# motion_detect.net
KiCad netlist of a schematic drawn in EAGLE
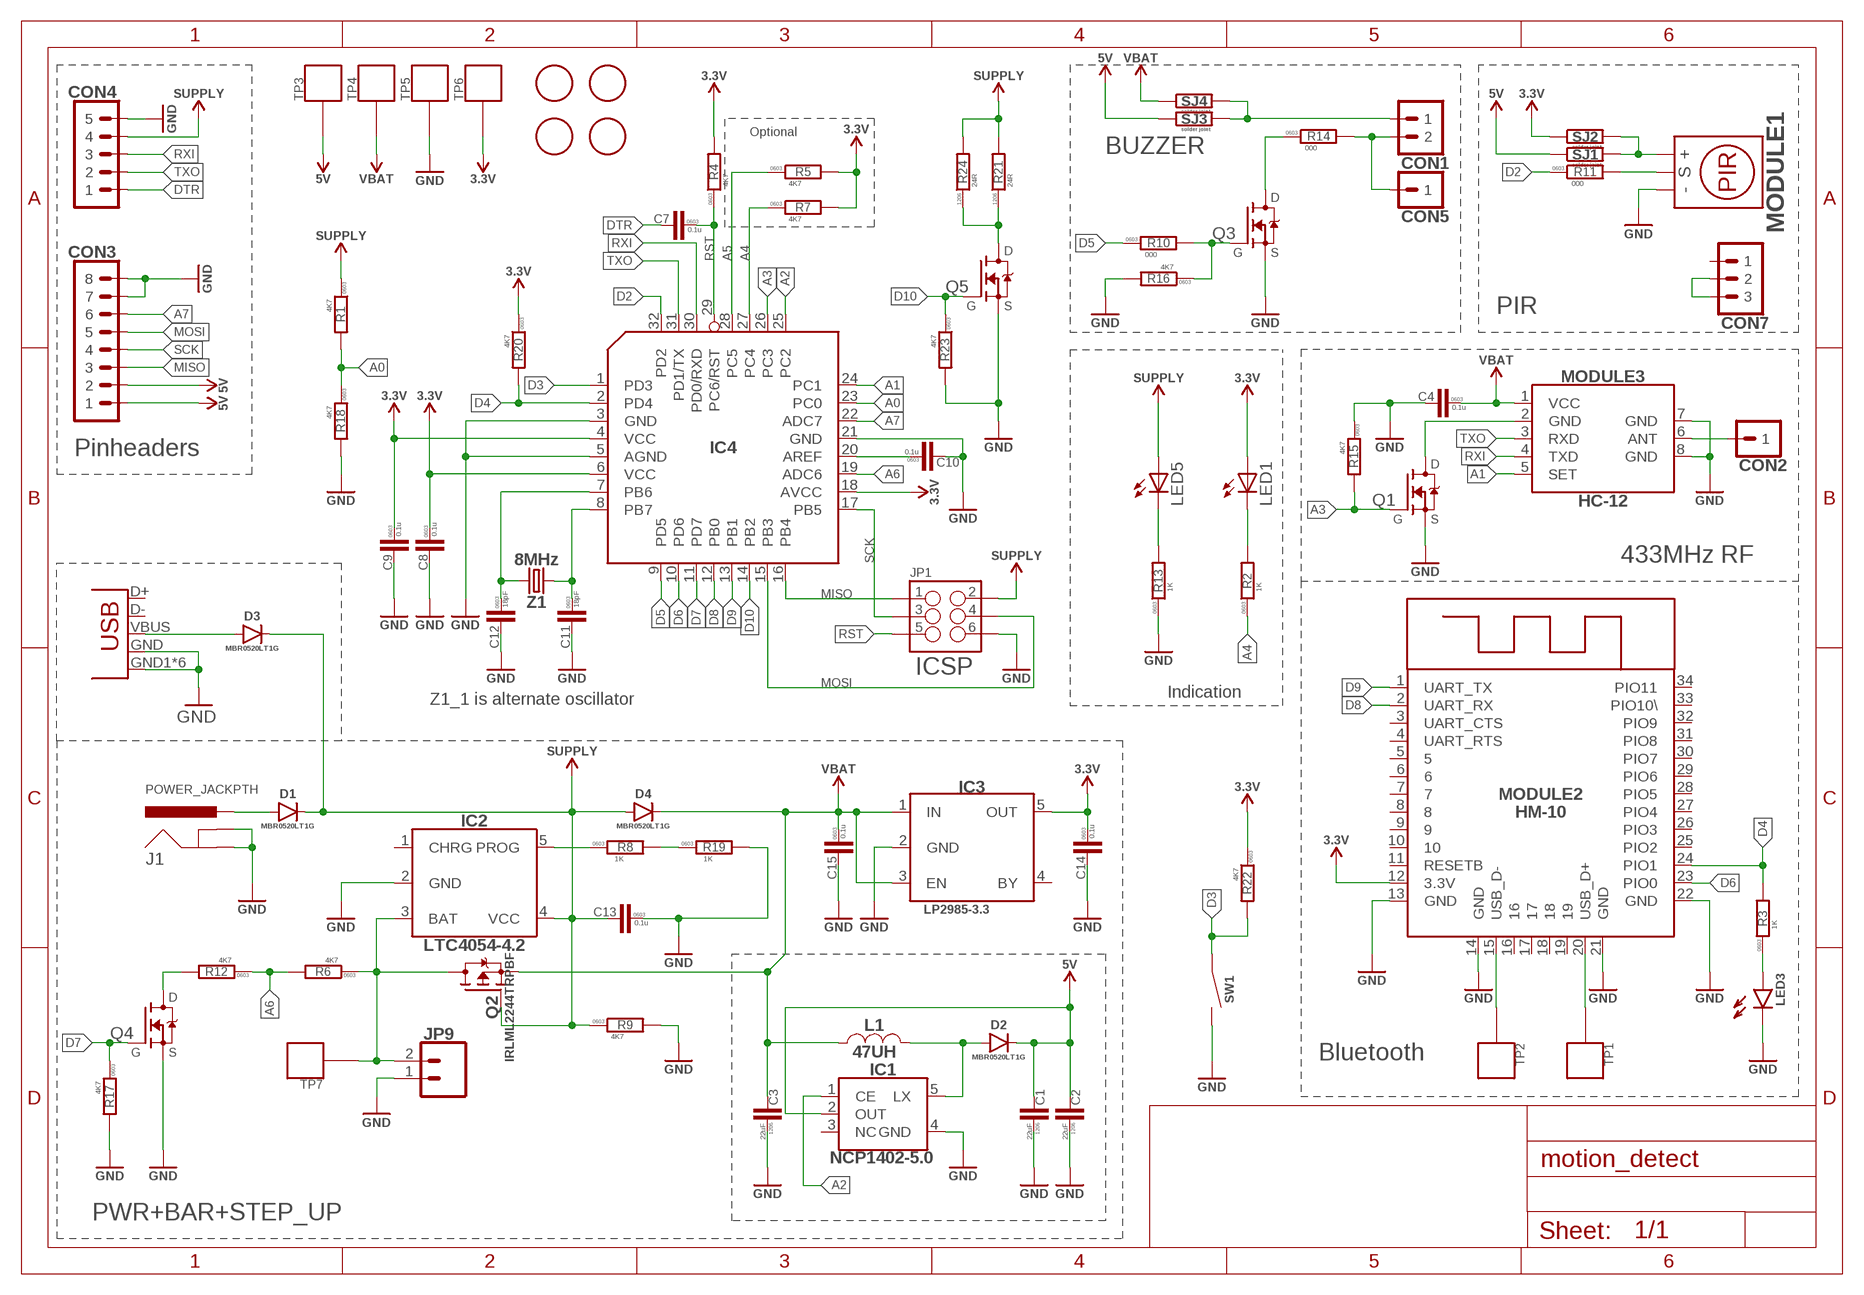
[diagram p0: schematic, sheet 1]

(export (version "E")
  (design (tool "Eeschema 10.0.6"))
  (components
    (comp (ref "C1")
      (value "22uF")
      (footprint "eagle-import:C1206")
      (libsource (lib "eagle-import") (part "C-1206"))
    )
    (comp (ref "C2")
      (value "22uF")
      (footprint "eagle-import:C1206")
      (libsource (lib "eagle-import") (part "C-1206"))
    )
    (comp (ref "C3")
      (value "22uF")
      (footprint "eagle-import:C1206")
      (libsource (lib "eagle-import") (part "C-1206"))
    )
    (comp (ref "C4")
      (value "0.1u")
      (footprint "eagle-import:C0603")
      (libsource (lib "eagle-import") (part "C-0603"))
    )
    (comp (ref "C7")
      (value "0.1u")
      (footprint "eagle-import:C0603")
      (libsource (lib "eagle-import") (part "C-0603"))
    )
    (comp (ref "C8")
      (value "0.1u")
      (footprint "eagle-import:C0603")
      (libsource (lib "eagle-import") (part "C-0603"))
    )
    (comp (ref "C9")
      (value "0.1u")
      (footprint "eagle-import:C0603")
      (libsource (lib "eagle-import") (part "C-0603"))
    )
    (comp (ref "C10")
      (value "0.1u")
      (footprint "eagle-import:C0603")
      (libsource (lib "eagle-import") (part "C-0603"))
    )
    (comp (ref "C11")
      (value "18pF")
      (footprint "eagle-import:C0603")
      (libsource (lib "eagle-import") (part "C-0603"))
    )
    (comp (ref "C12")
      (value "18pF")
      (footprint "eagle-import:C0603")
      (libsource (lib "eagle-import") (part "C-0603"))
    )
    (comp (ref "C13")
      (value "0.1u")
      (footprint "eagle-import:C0603")
      (libsource (lib "eagle-import") (part "C-0603"))
    )
    (comp (ref "C14")
      (value "0.1u")
      (footprint "eagle-import:C0603")
      (libsource (lib "eagle-import") (part "C-0603"))
    )
    (comp (ref "C15")
      (value "0.1u")
      (footprint "eagle-import:C0603")
      (libsource (lib "eagle-import") (part "C-0603"))
    )
    (comp (ref "CON1")
      (value "PINHEAD_1X02-2.54")
      (footprint "eagle-import:1X02-PTH-2.54")
      (libsource (lib "eagle-import") (part "PINHEAD_1X02-2.54"))
    )
    (comp (ref "CON2")
      (value "PINHEAD_1X01-2.54")
      (footprint "eagle-import:1X01-PTH-2.54")
      (libsource (lib "eagle-import") (part "PINHEAD_1X01-2.54"))
    )
    (comp (ref "CON3")
      (value "PINHEAD_1X08-2.54")
      (footprint "eagle-import:1X08-PTH-2.54")
      (libsource (lib "eagle-import") (part "PINHEAD_1X08-2.54"))
    )
    (comp (ref "CON4")
      (value "PINHEAD_1X05-2.54")
      (footprint "eagle-import:1X05-PTH-2.54")
      (libsource (lib "eagle-import") (part "PINHEAD_1X05-2.54"))
    )
    (comp (ref "CON5")
      (value "PINHEAD_1X01-2.54")
      (footprint "eagle-import:1X01-PTH-2.54")
      (libsource (lib "eagle-import") (part "PINHEAD_1X01-2.54"))
    )
    (comp (ref "CON6")
      (value "USB-2")
      (footprint "eagle-import:MICRO_USB_WITHOUT_PEGS")
      (fields (field (name "MANF") "FCI"))
      (libsource (lib "eagle-import") (part "USB-2"))
    )
    (comp (ref "CON7")
      (value "PINHEAD_1X03-2.54")
      (footprint "eagle-import:1X03-PTH-2.54")
      (libsource (lib "eagle-import") (part "PINHEAD_1X03-2.54"))
    )
    (comp (ref "D1")
      (value "MBR0520L-SOD123")
      (footprint "eagle-import:SOD123")
      (fields (field (name "MANF") "ON Semiconductor"))
      (libsource (lib "eagle-import") (part "MBR0520L-SOD123"))
    )
    (comp (ref "D2")
      (value "MBR0520L-SOD123")
      (footprint "eagle-import:SOD123")
      (fields (field (name "MANF") "ON Semiconductor"))
      (libsource (lib "eagle-import") (part "MBR0520L-SOD123"))
    )
    (comp (ref "D3")
      (value "MBR0520L-SOD123")
      (footprint "eagle-import:SOD123")
      (fields (field (name "MANF") "ON Semiconductor"))
      (libsource (lib "eagle-import") (part "MBR0520L-SOD123"))
    )
    (comp (ref "D4")
      (value "MBR0520L-SOD123")
      (footprint "eagle-import:SOD123")
      (fields (field (name "MANF") "ON Semiconductor"))
      (libsource (lib "eagle-import") (part "MBR0520L-SOD123"))
    )
    (comp (ref "IC1")
      (value "5.0")
      (footprint "eagle-import:SOT23-5")
      (fields (field (name "MANF") "ON Semiconductor"))
      (libsource (lib "eagle-import") (part "NCP1402-5V"))
    )
    (comp (ref "IC2")
      (value "LTC4054")
      (footprint "eagle-import:SOT23-5L")
      (fields (field (name "MANF") "Linear Technology"))
      (libsource (lib "eagle-import") (part "LTC4054"))
    )
    (comp (ref "IC3")
      (value "3.3")
      (footprint "eagle-import:SOT23-5L")
      (fields (field (name "MANF") "Texas Instruments"))
      (libsource (lib "eagle-import") (part "LP2985-3.3V"))
    )
    (comp (ref "IC4")
      (value "ATMEGA168-TQFP32")
      (footprint "eagle-import:TQFP32-08")
      (fields (field (name "MANF#") "ATMEGA168"))
      (libsource (lib "eagle-import") (part "ATMEGA168-TQFP32"))
    )
    (comp (ref "J1")
      (value "POWER_JACKPTH")
      (footprint "eagle-import:POWER_JACK_PTH")
      (libsource (lib "eagle-import") (part "POWER_JACKPTH"))
    )
    (comp (ref "JP1")
      (value "M03X2POGO_PINS")
      (footprint "eagle-import:2X3_POGO")
      (libsource (lib "eagle-import") (part "M03X2POGO_PINS"))
    )
    (comp (ref "JP9")
      (value "M02-B2B-PH-K-S")
      (footprint "eagle-import:JST-2-PTH")
      (fields (field (name "MANF") "B2B-PH-K-S(LF)(SN)"))
      (libsource (lib "eagle-import") (part "M02-B2B-PH-K-S"))
    )
    (comp (ref "L1")
      (value "47UH")
      (footprint "eagle-import:SDR0403")
      (libsource (lib "eagle-import") (part "INDUCTOR-SDR0403"))
    )
    (comp (ref "LED1")
      (value "LED-3MM")
      (footprint "eagle-import:LED-3MM")
      (libsource (lib "eagle-import") (part "LED-3MM"))
    )
    (comp (ref "LED3")
      (value "LED-0603")
      (footprint "eagle-import:LED0603")
      (fields (field (name "COLOR") "blue"))
      (libsource (lib "eagle-import") (part "rc_LED-0603"))
    )
    (comp (ref "LED5")
      (value "LED-3MM")
      (footprint "eagle-import:LED-3MM")
      (libsource (lib "eagle-import") (part "LED-3MM"))
    )
    (comp (ref "MODULE1")
      (value "MOTION-PIR-DYP-ME003")
      (footprint "eagle-import:MOTION-PIR-DYP-ME003")
      (libsource (lib "eagle-import") (part "MOTION-PIR-DYP-ME003"))
    )
    (comp (ref "MODULE2")
      (value "HM-10")
      (footprint "eagle-import:HM-10")
      (libsource (lib "eagle-import") (part "HM-10"))
    )
    (comp (ref "MODULE3")
      (value "HC12")
      (footprint "eagle-import:HC-12")
      (libsource (lib "eagle-import") (part "HC12"))
    )
    (comp (ref "Q1")
      (value "IRLML2502-SOT23")
      (footprint "eagle-import:SOT23B-3")
      (fields (field (name "MANF") "Infineon Technologies"))
      (libsource (lib "eagle-import") (part "IRLML2502-SOT23"))
    )
    (comp (ref "Q2")
      (value "IRLML2244TRPBF")
      (footprint "eagle-import:SOT23B-3")
      (fields (field (name "MANF") "Infineon Technologies"))
      (libsource (lib "eagle-import") (part "IRLML2244TRPBF"))
    )
    (comp (ref "Q3")
      (value "IRLML2502-SOT23")
      (footprint "eagle-import:SOT23B-3")
      (fields (field (name "MANF") "Infineon Technologies"))
      (libsource (lib "eagle-import") (part "IRLML2502-SOT23"))
    )
    (comp (ref "Q4")
      (value "IRLML2502-SOT23")
      (footprint "eagle-import:SOT23B-3")
      (fields (field (name "MANF") "Infineon Technologies"))
      (libsource (lib "eagle-import") (part "IRLML2502-SOT23"))
    )
    (comp (ref "Q5")
      (value "IRLML2502-SOT23")
      (footprint "eagle-import:SOT23B-3")
      (fields (field (name "MANF") "Infineon Technologies"))
      (libsource (lib "eagle-import") (part "IRLML2502-SOT23"))
    )
    (comp (ref "R1")
      (value "4K7")
      (footprint "eagle-import:R0603")
      (libsource (lib "eagle-import") (part "R-0603"))
    )
    (comp (ref "R2")
      (value "1K")
      (footprint "eagle-import:R0603")
      (libsource (lib "eagle-import") (part "R-0603"))
    )
    (comp (ref "R3")
      (value "1K")
      (footprint "eagle-import:R0603")
      (libsource (lib "eagle-import") (part "R-0603"))
    )
    (comp (ref "R4")
      (value "4K7")
      (footprint "eagle-import:R0603")
      (libsource (lib "eagle-import") (part "R-0603"))
    )
    (comp (ref "R5")
      (value "4K7")
      (footprint "eagle-import:R0603")
      (libsource (lib "eagle-import") (part "R-0603"))
    )
    (comp (ref "R6")
      (value "4K7")
      (footprint "eagle-import:R0603")
      (libsource (lib "eagle-import") (part "R-0603"))
    )
    (comp (ref "R7")
      (value "4K7")
      (footprint "eagle-import:R0603")
      (libsource (lib "eagle-import") (part "R-0603"))
    )
    (comp (ref "R8")
      (value "1K")
      (footprint "eagle-import:R0603")
      (libsource (lib "eagle-import") (part "R-0603"))
    )
    (comp (ref "R9")
      (value "4K7")
      (footprint "eagle-import:R0603")
      (libsource (lib "eagle-import") (part "R-0603"))
    )
    (comp (ref "R10")
      (value "000")
      (footprint "eagle-import:R0603")
      (libsource (lib "eagle-import") (part "R-0603"))
    )
    (comp (ref "R11")
      (value "000")
      (footprint "eagle-import:R0603")
      (libsource (lib "eagle-import") (part "R-0603"))
    )
    (comp (ref "R12")
      (value "4K7")
      (footprint "eagle-import:R0603")
      (libsource (lib "eagle-import") (part "R-0603"))
    )
    (comp (ref "R13")
      (value "1K")
      (footprint "eagle-import:R0603")
      (libsource (lib "eagle-import") (part "R-0603"))
    )
    (comp (ref "R14")
      (value "000")
      (footprint "eagle-import:R0603")
      (libsource (lib "eagle-import") (part "R-0603"))
    )
    (comp (ref "R15")
      (value "4K7")
      (footprint "eagle-import:R0603")
      (libsource (lib "eagle-import") (part "R-0603"))
    )
    (comp (ref "R16")
      (value "4K7")
      (footprint "eagle-import:R0603")
      (libsource (lib "eagle-import") (part "R-0603"))
    )
    (comp (ref "R17")
      (value "4K7")
      (footprint "eagle-import:R0603")
      (libsource (lib "eagle-import") (part "R-0603"))
    )
    (comp (ref "R18")
      (value "4K7")
      (footprint "eagle-import:R0603")
      (libsource (lib "eagle-import") (part "R-0603"))
    )
    (comp (ref "R19")
      (value "1K")
      (footprint "eagle-import:R0603")
      (libsource (lib "eagle-import") (part "R-0603"))
    )
    (comp (ref "R20")
      (value "4K7")
      (footprint "eagle-import:R0603")
      (libsource (lib "eagle-import") (part "R-0603"))
    )
    (comp (ref "R21")
      (value "24R")
      (footprint "eagle-import:R1206")
      (libsource (lib "eagle-import") (part "R-R1206"))
    )
    (comp (ref "R22")
      (value "4K7")
      (footprint "eagle-import:R0603")
      (libsource (lib "eagle-import") (part "R-0603"))
    )
    (comp (ref "R23")
      (value "4K7")
      (footprint "eagle-import:R0603")
      (libsource (lib "eagle-import") (part "R-0603"))
    )
    (comp (ref "R24")
      (value "24R")
      (footprint "eagle-import:R1206")
      (libsource (lib "eagle-import") (part "R-R1206"))
    )
    (comp (ref "SJ1")
      (value "SOLDER_JOINT")
      (footprint "eagle-import:RES_0")
      (libsource (lib "eagle-import") (part "SOLDER_JOINT"))
    )
    (comp (ref "SJ2")
      (value "SOLDER_JOINT")
      (footprint "eagle-import:RES_0")
      (libsource (lib "eagle-import") (part "SOLDER_JOINT"))
    )
    (comp (ref "SJ3")
      (value "SOLDER_JOINT")
      (footprint "eagle-import:RES_0")
      (libsource (lib "eagle-import") (part "SOLDER_JOINT"))
    )
    (comp (ref "SJ4")
      (value "SOLDER_JOINT")
      (footprint "eagle-import:RES_0")
      (libsource (lib "eagle-import") (part "SOLDER_JOINT"))
    )
    (comp (ref "SW1")
      (value "TACT_SWITCH-TC-206")
      (footprint "eagle-import:TC-0206")
      (libsource (lib "eagle-import") (part "TACT_SWITCH-TC-206"))
    )
    (comp (ref "TP1")
      (value "PAD.05")
      (footprint "eagle-import:PAD.05X.05")
      (libsource (lib "eagle-import") (part "PAD.05"))
    )
    (comp (ref "TP2")
      (value "PAD.05")
      (footprint "eagle-import:PAD.05X.05")
      (libsource (lib "eagle-import") (part "PAD.05"))
    )
    (comp (ref "TP3")
      (value "PAD.05")
      (footprint "eagle-import:PAD.05X.05")
      (libsource (lib "eagle-import") (part "PAD.05"))
    )
    (comp (ref "TP4")
      (value "PAD.05")
      (footprint "eagle-import:PAD.05X.05")
      (libsource (lib "eagle-import") (part "PAD.05"))
    )
    (comp (ref "TP5")
      (value "PAD.05")
      (footprint "eagle-import:PAD.05X.05")
      (libsource (lib "eagle-import") (part "PAD.05"))
    )
    (comp (ref "TP6")
      (value "PAD.05")
      (footprint "eagle-import:PAD.05X.05")
      (libsource (lib "eagle-import") (part "PAD.05"))
    )
    (comp (ref "TP7")
      (value "PAD.05")
      (footprint "eagle-import:PAD.05X.05")
      (libsource (lib "eagle-import") (part "PAD.05"))
    )
    (comp (ref "U$3")
      (value "FIDUCIALMOUNT")
      (footprint "eagle-import:FIDUCIA-MOUNT")
      (libsource (lib "eagle-import") (part "FIDUCIALMOUNT"))
    )
    (comp (ref "U$4")
      (value "FIDUCIALMOUNT")
      (footprint "eagle-import:FIDUCIA-MOUNT")
      (libsource (lib "eagle-import") (part "FIDUCIALMOUNT"))
    )
    (comp (ref "U$5")
      (value "FIDUCIALMOUNT")
      (footprint "eagle-import:FIDUCIA-MOUNT")
      (libsource (lib "eagle-import") (part "FIDUCIALMOUNT"))
    )
    (comp (ref "U$6")
      (value "FIDUCIALMOUNT")
      (footprint "eagle-import:FIDUCIA-MOUNT")
      (libsource (lib "eagle-import") (part "FIDUCIALMOUNT"))
    )
    (comp (ref "Z1")
      (value "8MHz")
      (footprint "eagle-import:HC49UP")
      (fields (field (name "MANF") "Abracon LLC"))
      (libsource (lib "eagle-import") (part "CRYSTAL-8MHZHC49UP"))
    )
  )
  (nets
    (net (code "1") (name "/A5") (class "Default")
      (node (ref "IC4") (pin "28") (pinfunction "PC5_28") (pintype "bidirectional"))
      (node (ref "R5") (pin "1") (pinfunction "1_1") (pintype "passive"))
    )
    (net (code "2") (name "3.3V") (class "Default")
      (node (ref "C14") (pin "1") (pinfunction "1_1") (pintype "passive"))
      (node (ref "C8") (pin "1") (pinfunction "1_1") (pintype "passive"))
      (node (ref "C9") (pin "1") (pinfunction "1_1") (pintype "passive"))
      (node (ref "IC3") (pin "5") (pinfunction "OUT_5") (pintype "bidirectional"))
      (node (ref "IC4") (pin "18") (pinfunction "AVCC_18") (pintype "bidirectional"))
      (node (ref "IC4") (pin "4") (pinfunction "VCC_4") (pintype "bidirectional"))
      (node (ref "IC4") (pin "6") (pinfunction "VCC_6") (pintype "bidirectional"))
      (node (ref "LED1") (pin "A") (pinfunction "A_A") (pintype "passive"))
      (node (ref "MODULE2") (pin "12") (pinfunction "3.3V_12") (pintype "bidirectional"))
      (node (ref "R20") (pin "1") (pinfunction "1_1") (pintype "passive"))
      (node (ref "R22") (pin "1") (pinfunction "1_1") (pintype "passive"))
      (node (ref "R4") (pin "2") (pinfunction "2_2") (pintype "passive"))
      (node (ref "R5") (pin "2") (pinfunction "2_2") (pintype "passive"))
      (node (ref "R7") (pin "2") (pinfunction "2_2") (pintype "passive"))
      (node (ref "SJ2") (pin "1") (pinfunction "1_1") (pintype "passive"))
      (node (ref "TP6") (pin "P$1") (pinfunction "P$1_P$1") (pintype "passive"))
    )
    (net (code "3") (name "5V") (class "Default")
      (node (ref "C1") (pin "P$2") (pinfunction "2_P$2") (pintype "passive"))
      (node (ref "C2") (pin "P$2") (pinfunction "2_P$2") (pintype "passive"))
      (node (ref "CON3") (pin "1") (pinfunction "1_1") (pintype "passive"))
      (node (ref "CON3") (pin "2") (pinfunction "2_2") (pintype "passive"))
      (node (ref "D2") (pin "C") (pinfunction "C_C") (pintype "passive"))
      (node (ref "IC1") (pin "2") (pinfunction "OUT_2") (pintype "bidirectional"))
      (node (ref "SJ1") (pin "1") (pinfunction "1_1") (pintype "passive"))
      (node (ref "SJ3") (pin "1") (pinfunction "1_1") (pintype "passive"))
      (node (ref "TP3") (pin "P$1") (pinfunction "P$1_P$1") (pintype "passive"))
    )
    (net (code "4") (name "A0") (class "Default")
      (node (ref "IC4") (pin "23") (pinfunction "PC0_23") (pintype "bidirectional"))
      (node (ref "R1") (pin "2") (pinfunction "2_2") (pintype "passive"))
      (node (ref "R18") (pin "1") (pinfunction "1_1") (pintype "passive"))
    )
    (net (code "5") (name "A1") (class "Default")
      (node (ref "IC4") (pin "24") (pinfunction "PC1_24") (pintype "bidirectional"))
      (node (ref "MODULE3") (pin "5") (pinfunction "SET_5") (pintype "input"))
    )
    (net (code "6") (name "A2") (class "Default")
      (node (ref "IC1") (pin "1") (pinfunction "CE_1") (pintype "bidirectional"))
      (node (ref "IC4") (pin "25") (pinfunction "PC2_25") (pintype "bidirectional"))
    )
    (net (code "7") (name "A3") (class "Default")
      (node (ref "IC4") (pin "26") (pinfunction "PC3_26") (pintype "bidirectional"))
      (node (ref "Q1") (pin "1") (pinfunction "G_1") (pintype "passive"))
      (node (ref "R15") (pin "2") (pinfunction "2_2") (pintype "passive"))
    )
    (net (code "8") (name "A4") (class "Default")
      (node (ref "IC4") (pin "27") (pinfunction "PC4_27") (pintype "bidirectional"))
      (node (ref "R2") (pin "1") (pinfunction "1_1") (pintype "passive"))
      (node (ref "R7") (pin "1") (pinfunction "1_1") (pintype "passive"))
    )
    (net (code "9") (name "A6") (class "Default")
      (node (ref "IC4") (pin "19") (pinfunction "ADC6_19") (pintype "bidirectional"))
      (node (ref "R12") (pin "1") (pinfunction "1_1") (pintype "passive"))
      (node (ref "R6") (pin "2") (pinfunction "2_2") (pintype "passive"))
    )
    (net (code "10") (name "A7") (class "Default")
      (node (ref "CON3") (pin "6") (pinfunction "6_6") (pintype "passive"))
      (node (ref "IC4") (pin "22") (pinfunction "ADC7_22") (pintype "bidirectional"))
    )
    (net (code "11") (name "D2") (class "Default")
      (node (ref "IC4") (pin "32") (pinfunction "PD2_32") (pintype "bidirectional"))
      (node (ref "R11") (pin "1") (pinfunction "1_1") (pintype "passive"))
    )
    (net (code "12") (name "D3") (class "Default")
      (node (ref "IC4") (pin "1") (pinfunction "PD3_1") (pintype "bidirectional"))
      (node (ref "R22") (pin "2") (pinfunction "2_2") (pintype "passive"))
      (node (ref "SW1") (pin "1") (pinfunction "1_1") (pintype "bidirectional"))
    )
    (net (code "13") (name "D4") (class "Default")
      (node (ref "IC4") (pin "2") (pinfunction "PD4_2") (pintype "bidirectional"))
      (node (ref "MODULE2") (pin "24") (pinfunction "PIO1_24") (pintype "bidirectional"))
      (node (ref "R20") (pin "2") (pinfunction "2_2") (pintype "passive"))
      (node (ref "R3") (pin "2") (pinfunction "2_2") (pintype "passive"))
    )
    (net (code "14") (name "D5") (class "Default")
      (node (ref "IC4") (pin "9") (pinfunction "PD5_9") (pintype "bidirectional"))
      (node (ref "R10") (pin "1") (pinfunction "1_1") (pintype "passive"))
    )
    (net (code "15") (name "D6") (class "Default")
      (node (ref "IC4") (pin "10") (pinfunction "PD6_10") (pintype "bidirectional"))
      (node (ref "MODULE2") (pin "23") (pinfunction "PIO0_23") (pintype "bidirectional"))
    )
    (net (code "16") (name "D7") (class "Default")
      (node (ref "IC4") (pin "11") (pinfunction "PD7_11") (pintype "bidirectional"))
      (node (ref "Q4") (pin "1") (pinfunction "G_1") (pintype "passive"))
      (node (ref "R17") (pin "1") (pinfunction "1_1") (pintype "passive"))
    )
    (net (code "17") (name "D8") (class "Default")
      (node (ref "IC4") (pin "12") (pinfunction "PB0_12") (pintype "bidirectional"))
      (node (ref "MODULE2") (pin "2") (pinfunction "UART_RX_2") (pintype "bidirectional"))
    )
    (net (code "18") (name "D9") (class "Default")
      (node (ref "IC4") (pin "13") (pinfunction "PB1_13") (pintype "bidirectional"))
      (node (ref "MODULE2") (pin "1") (pinfunction "UART_TX_1") (pintype "bidirectional"))
    )
    (net (code "19") (name "D10") (class "Default")
      (node (ref "IC4") (pin "14") (pinfunction "PB2_14") (pintype "bidirectional"))
      (node (ref "Q5") (pin "1") (pinfunction "G_1") (pintype "passive"))
      (node (ref "R23") (pin "1") (pinfunction "1_1") (pintype "passive"))
    )
    (net (code "20") (name "DTR") (class "Default")
      (node (ref "C7") (pin "2") (pinfunction "2_2") (pintype "passive"))
      (node (ref "CON4") (pin "1") (pinfunction "1_1") (pintype "passive"))
    )
    (net (code "21") (name "GND") (class "Default")
      (node (ref "C1") (pin "P$1") (pinfunction "1_P$1") (pintype "passive"))
      (node (ref "C10") (pin "2") (pinfunction "2_2") (pintype "passive"))
      (node (ref "C11") (pin "2") (pinfunction "2_2") (pintype "passive"))
      (node (ref "C12") (pin "2") (pinfunction "2_2") (pintype "passive"))
      (node (ref "C13") (pin "1") (pinfunction "1_1") (pintype "passive"))
      (node (ref "C14") (pin "2") (pinfunction "2_2") (pintype "passive"))
      (node (ref "C15") (pin "2") (pinfunction "2_2") (pintype "passive"))
      (node (ref "C2") (pin "P$1") (pinfunction "1_P$1") (pintype "passive"))
      (node (ref "C3") (pin "P$1") (pinfunction "1_P$1") (pintype "passive"))
      (node (ref "C4") (pin "2") (pinfunction "2_2") (pintype "passive"))
      (node (ref "C8") (pin "2") (pinfunction "2_2") (pintype "passive"))
      (node (ref "C9") (pin "2") (pinfunction "2_2") (pintype "passive"))
      (node (ref "CON3") (pin "7") (pinfunction "7_7") (pintype "passive"))
      (node (ref "CON3") (pin "8") (pinfunction "8_8") (pintype "passive"))
      (node (ref "CON4") (pin "5") (pinfunction "5_5") (pintype "passive"))
      (node (ref "CON6") (pin "GND") (pinfunction "GND_GND") (pintype "bidirectional"))
      (node (ref "CON6") (pin "GND1") (pinfunction "SHIELD_GND1") (pintype "bidirectional"))
      (node (ref "CON6") (pin "GND2") (pinfunction "SHIELD_GND2") (pintype "bidirectional"))
      (node (ref "CON6") (pin "GND3") (pinfunction "SHIELD_GND3") (pintype "bidirectional"))
      (node (ref "CON6") (pin "GND4") (pinfunction "SHIELD_GND4") (pintype "bidirectional"))
      (node (ref "CON6") (pin "GND5") (pinfunction "SHIELD_GND5") (pintype "bidirectional"))
      (node (ref "CON6") (pin "GND6") (pinfunction "SHIELD_GND6") (pintype "bidirectional"))
      (node (ref "IC1") (pin "4") (pinfunction "GND_4") (pintype "bidirectional"))
      (node (ref "IC2") (pin "2") (pinfunction "GND_2") (pintype "bidirectional"))
      (node (ref "IC3") (pin "2") (pinfunction "GND_2") (pintype "bidirectional"))
      (node (ref "IC4") (pin "21") (pinfunction "GND_21") (pintype "bidirectional"))
      (node (ref "IC4") (pin "3") (pinfunction "GND_3") (pintype "bidirectional"))
      (node (ref "IC4") (pin "5") (pinfunction "AGND_5") (pintype "bidirectional"))
      (node (ref "J1") (pin "GND") (pinfunction "GND_GND") (pintype "bidirectional"))
      (node (ref "J1") (pin "GNDBREAK") (pinfunction "GNDBREAK_GNDBREAK") (pintype "bidirectional"))
      (node (ref "JP1") (pin "P$6") (pinfunction "6_P$6") (pintype "bidirectional"))
      (node (ref "JP9") (pin "1") (pinfunction "1_1") (pintype "passive"))
      (node (ref "LED3") (pin "C") (pinfunction "C_C") (pintype "bidirectional"))
      (node (ref "MODULE1") (pin "1") (pinfunction "GND_1") (pintype "power_in"))
      (node (ref "MODULE2") (pin "13") (pinfunction "GND_13") (pintype "bidirectional"))
      (node (ref "MODULE2") (pin "14") (pinfunction "GND_14") (pintype "bidirectional"))
      (node (ref "MODULE2") (pin "21") (pinfunction "GND_21") (pintype "bidirectional"))
      (node (ref "MODULE2") (pin "22") (pinfunction "GND_22") (pintype "bidirectional"))
      (node (ref "MODULE3") (pin "7") (pinfunction "GND_7") (pintype "power_in"))
      (node (ref "MODULE3") (pin "8") (pinfunction "GND_8") (pintype "power_in"))
      (node (ref "Q1") (pin "2") (pinfunction "S_2") (pintype "passive"))
      (node (ref "Q3") (pin "2") (pinfunction "S_2") (pintype "passive"))
      (node (ref "Q4") (pin "2") (pinfunction "S_2") (pintype "passive"))
      (node (ref "Q5") (pin "2") (pinfunction "S_2") (pintype "passive"))
      (node (ref "R13") (pin "1") (pinfunction "1_1") (pintype "passive"))
      (node (ref "R15") (pin "1") (pinfunction "1_1") (pintype "passive"))
      (node (ref "R16") (pin "2") (pinfunction "2_2") (pintype "passive"))
      (node (ref "R17") (pin "2") (pinfunction "2_2") (pintype "passive"))
      (node (ref "R18") (pin "2") (pinfunction "2_2") (pintype "passive"))
      (node (ref "R19") (pin "2") (pinfunction "2_2") (pintype "passive"))
      (node (ref "R23") (pin "2") (pinfunction "2_2") (pintype "passive"))
      (node (ref "R9") (pin "2") (pinfunction "2_2") (pintype "passive"))
      (node (ref "SW1") (pin "2") (pinfunction "2_2") (pintype "bidirectional"))
      (node (ref "TP5") (pin "P$1") (pinfunction "P$1_P$1") (pintype "passive"))
    )
    (net (code "22") (name "MISO") (class "Default")
      (node (ref "CON3") (pin "3") (pinfunction "3_3") (pintype "passive"))
      (node (ref "IC4") (pin "16") (pinfunction "PB4_16") (pintype "bidirectional"))
      (node (ref "JP1") (pin "P$1") (pinfunction "1_P$1") (pintype "bidirectional"))
    )
    (net (code "23") (name "MOSI") (class "Default")
      (node (ref "CON3") (pin "5") (pinfunction "5_5") (pintype "passive"))
      (node (ref "IC4") (pin "15") (pinfunction "PB3_15") (pintype "bidirectional"))
      (node (ref "JP1") (pin "P$4") (pinfunction "4_P$4") (pintype "bidirectional"))
    )
    (net (code "24") (name "Net-(CON1-Pad1)") (class "Default")
      (node (ref "CON1") (pin "1") (pinfunction "1_1") (pintype "passive"))
      (node (ref "SJ3") (pin "2") (pinfunction "2_2") (pintype "passive"))
      (node (ref "SJ4") (pin "2") (pinfunction "2_2") (pintype "passive"))
    )
    (net (code "25") (name "Net-(CON1-Pad2)") (class "Default")
      (node (ref "CON1") (pin "2") (pinfunction "2_2") (pintype "passive"))
      (node (ref "CON5") (pin "1") (pinfunction "1_1") (pintype "passive"))
      (node (ref "R14") (pin "2") (pinfunction "2_2") (pintype "passive"))
    )
    (net (code "26") (name "Net-(CON6-PadVBUS)") (class "Default")
      (node (ref "CON6") (pin "VBUS") (pinfunction "VBUS_VBUS") (pintype "bidirectional"))
      (node (ref "D3") (pin "A") (pinfunction "A_A") (pintype "passive"))
    )
    (net (code "27") (name "Net-(CON7-Pad2)") (class "Default")
      (node (ref "CON7") (pin "2") (pinfunction "2_2") (pintype "passive"))
      (node (ref "CON7") (pin "3") (pinfunction "3_3") (pintype "passive"))
    )
    (net (code "28") (name "Net-(D1-PadA)") (class "Default")
      (node (ref "D1") (pin "A") (pinfunction "A_A") (pintype "passive"))
      (node (ref "J1") (pin "PWR") (pinfunction "PWR_PWR") (pintype "bidirectional"))
    )
    (net (code "29") (name "Net-(IC1-LX)") (class "Default")
      (node (ref "D2") (pin "A") (pinfunction "A_A") (pintype "passive"))
      (node (ref "IC1") (pin "5") (pinfunction "LX_5") (pintype "bidirectional"))
      (node (ref "L1") (pin "P$2") (pinfunction "2_P$2") (pintype "passive"))
    )
    (net (code "30") (name "Net-(IC2-BAT)") (class "Default")
      (node (ref "IC2") (pin "3") (pinfunction "BAT_3") (pintype "bidirectional"))
      (node (ref "JP9") (pin "2") (pinfunction "2_2") (pintype "passive"))
      (node (ref "Q2") (pin "3") (pinfunction "D_3") (pintype "passive"))
      (node (ref "R6") (pin "1") (pinfunction "1_1") (pintype "passive"))
      (node (ref "TP7") (pin "P$1") (pinfunction "P$1_P$1") (pintype "passive"))
    )
    (net (code "31") (name "Net-(IC2-PROG)") (class "Default")
      (node (ref "IC2") (pin "5") (pinfunction "PROG_5") (pintype "bidirectional"))
      (node (ref "R8") (pin "1") (pinfunction "1_1") (pintype "passive"))
    )
    (net (code "32") (name "Net-(IC4-AREF)") (class "Default")
      (node (ref "C10") (pin "1") (pinfunction "1_1") (pintype "passive"))
      (node (ref "IC4") (pin "20") (pinfunction "AREF_20") (pintype "bidirectional"))
    )
    (net (code "33") (name "Net-(IC4-PB6)") (class "Default")
      (node (ref "C12") (pin "1") (pinfunction "1_1") (pintype "passive"))
      (node (ref "IC4") (pin "7") (pinfunction "PB6_7") (pintype "bidirectional"))
      (node (ref "Z1") (pin "2") (pinfunction "2_2") (pintype "passive"))
    )
    (net (code "34") (name "Net-(IC4-PB7)") (class "Default")
      (node (ref "C11") (pin "1") (pinfunction "1_1") (pintype "passive"))
      (node (ref "IC4") (pin "8") (pinfunction "PB7_8") (pintype "bidirectional"))
      (node (ref "Z1") (pin "1") (pinfunction "1_1") (pintype "passive"))
    )
    (net (code "35") (name "Net-(LED1-C)") (class "Default")
      (node (ref "LED1") (pin "K") (pinfunction "C_K") (pintype "passive"))
      (node (ref "R2") (pin "2") (pinfunction "2_2") (pintype "passive"))
    )
    (net (code "36") (name "Net-(LED3-PadA)") (class "Default")
      (node (ref "LED3") (pin "A") (pinfunction "A_A") (pintype "bidirectional"))
      (node (ref "R3") (pin "1") (pinfunction "1_1") (pintype "passive"))
    )
    (net (code "37") (name "Net-(LED5-C)") (class "Default")
      (node (ref "LED5") (pin "K") (pinfunction "C_K") (pintype "passive"))
      (node (ref "R13") (pin "2") (pinfunction "2_2") (pintype "passive"))
    )
    (net (code "38") (name "Net-(MODULE1-OUT)") (class "Default")
      (node (ref "MODULE1") (pin "2") (pinfunction "OUT_2") (pintype "output"))
      (node (ref "R11") (pin "2") (pinfunction "2_2") (pintype "passive"))
    )
    (net (code "39") (name "Net-(MODULE1-VCC)") (class "Default")
      (node (ref "MODULE1") (pin "3") (pinfunction "VCC_3") (pintype "power_in"))
      (node (ref "SJ1") (pin "2") (pinfunction "2_2") (pintype "passive"))
      (node (ref "SJ2") (pin "2") (pinfunction "2_2") (pintype "passive"))
    )
    (net (code "40") (name "Net-(MODULE2-USB_D+)") (class "Default")
      (node (ref "MODULE2") (pin "20") (pinfunction "USB_D+_20") (pintype "bidirectional"))
      (node (ref "TP1") (pin "P$1") (pinfunction "P$1_P$1") (pintype "passive"))
    )
    (net (code "41") (name "Net-(MODULE2-USB_D-)") (class "Default")
      (node (ref "MODULE2") (pin "15") (pinfunction "USB_D-_15") (pintype "bidirectional"))
      (node (ref "TP2") (pin "P$1") (pinfunction "P$1_P$1") (pintype "passive"))
    )
    (net (code "42") (name "Net-(MODULE3-ANT)") (class "Default")
      (node (ref "CON2") (pin "1") (pinfunction "1_1") (pintype "passive"))
      (node (ref "MODULE3") (pin "6") (pinfunction "ANT_6") (pintype "bidirectional"))
    )
    (net (code "43") (name "Net-(Q1-D)") (class "Default")
      (node (ref "MODULE3") (pin "2") (pinfunction "GND_2") (pintype "power_in"))
      (node (ref "Q1") (pin "3") (pinfunction "D_3") (pintype "passive"))
    )
    (net (code "44") (name "Net-(Q3-D)") (class "Default")
      (node (ref "Q3") (pin "3") (pinfunction "D_3") (pintype "passive"))
      (node (ref "R14") (pin "1") (pinfunction "1_1") (pintype "passive"))
    )
    (net (code "45") (name "Net-(Q3-G)") (class "Default")
      (node (ref "Q3") (pin "1") (pinfunction "G_1") (pintype "passive"))
      (node (ref "R10") (pin "2") (pinfunction "2_2") (pintype "passive"))
      (node (ref "R16") (pin "1") (pinfunction "1_1") (pintype "passive"))
    )
    (net (code "46") (name "Net-(Q4-D)") (class "Default")
      (node (ref "Q4") (pin "3") (pinfunction "D_3") (pintype "passive"))
      (node (ref "R12") (pin "2") (pinfunction "2_2") (pintype "passive"))
    )
    (net (code "47") (name "Net-(Q5-D)") (class "Default")
      (node (ref "Q5") (pin "3") (pinfunction "D_3") (pintype "passive"))
      (node (ref "R21") (pin "P$1") (pinfunction "1_P$1") (pintype "passive"))
      (node (ref "R24") (pin "P$1") (pinfunction "1_P$1") (pintype "passive"))
    )
    (net (code "48") (name "Net-(R19-Pad1)") (class "Default")
      (node (ref "R19") (pin "1") (pinfunction "1_1") (pintype "passive"))
      (node (ref "R8") (pin "2") (pinfunction "2_2") (pintype "passive"))
    )
    (net (code "49") (name "RST") (class "Default")
      (node (ref "C7") (pin "1") (pinfunction "1_1") (pintype "passive"))
      (node (ref "IC4") (pin "29") (pinfunction "PC6/RST_29") (pintype "bidirectional"))
      (node (ref "JP1") (pin "P$5") (pinfunction "5_P$5") (pintype "bidirectional"))
      (node (ref "R4") (pin "1") (pinfunction "1_1") (pintype "passive"))
    )
    (net (code "50") (name "RXI") (class "Default")
      (node (ref "CON4") (pin "3") (pinfunction "3_3") (pintype "passive"))
      (node (ref "IC4") (pin "30") (pinfunction "PD0/RXD_30") (pintype "bidirectional"))
      (node (ref "MODULE3") (pin "4") (pinfunction "TXD_4") (pintype "output"))
    )
    (net (code "51") (name "SCK") (class "Default")
      (node (ref "CON3") (pin "4") (pinfunction "4_4") (pintype "passive"))
      (node (ref "IC4") (pin "17") (pinfunction "PB5_17") (pintype "bidirectional"))
      (node (ref "JP1") (pin "P$3") (pinfunction "3_P$3") (pintype "bidirectional"))
    )
    (net (code "52") (name "SUPPLY") (class "Default")
      (node (ref "C13") (pin "2") (pinfunction "2_2") (pintype "passive"))
      (node (ref "CON4") (pin "4") (pinfunction "4_4") (pintype "passive"))
      (node (ref "D1") (pin "C") (pinfunction "C_C") (pintype "passive"))
      (node (ref "D3") (pin "C") (pinfunction "C_C") (pintype "passive"))
      (node (ref "D4") (pin "A") (pinfunction "A_A") (pintype "passive"))
      (node (ref "IC2") (pin "4") (pinfunction "VCC_4") (pintype "bidirectional"))
      (node (ref "JP1") (pin "P$2") (pinfunction "2_P$2") (pintype "bidirectional"))
      (node (ref "LED5") (pin "A") (pinfunction "A_A") (pintype "passive"))
      (node (ref "Q2") (pin "1") (pinfunction "G_1") (pintype "passive"))
      (node (ref "R1") (pin "1") (pinfunction "1_1") (pintype "passive"))
      (node (ref "R21") (pin "P$2") (pinfunction "2_P$2") (pintype "passive"))
      (node (ref "R24") (pin "P$2") (pinfunction "2_P$2") (pintype "passive"))
      (node (ref "R9") (pin "1") (pinfunction "1_1") (pintype "passive"))
    )
    (net (code "53") (name "TXO") (class "Default")
      (node (ref "CON4") (pin "2") (pinfunction "2_2") (pintype "passive"))
      (node (ref "IC4") (pin "31") (pinfunction "PD1/TX_31") (pintype "bidirectional"))
      (node (ref "MODULE3") (pin "3") (pinfunction "RXD_3") (pintype "input"))
    )
    (net (code "54") (name "VBAT") (class "Default")
      (node (ref "C15") (pin "1") (pinfunction "1_1") (pintype "passive"))
      (node (ref "C3") (pin "P$2") (pinfunction "2_P$2") (pintype "passive"))
      (node (ref "C4") (pin "1") (pinfunction "1_1") (pintype "passive"))
      (node (ref "D4") (pin "C") (pinfunction "C_C") (pintype "passive"))
      (node (ref "IC3") (pin "1") (pinfunction "IN_1") (pintype "bidirectional"))
      (node (ref "IC3") (pin "3") (pinfunction "EN_3") (pintype "bidirectional"))
      (node (ref "L1") (pin "P$1") (pinfunction "1_P$1") (pintype "passive"))
      (node (ref "MODULE3") (pin "1") (pinfunction "VCC_1") (pintype "bidirectional"))
      (node (ref "Q2") (pin "2") (pinfunction "S_2") (pintype "passive"))
      (node (ref "SJ4") (pin "1") (pinfunction "1_1") (pintype "passive"))
      (node (ref "TP4") (pin "P$1") (pinfunction "P$1_P$1") (pintype "passive"))
    )
    (net (code "55") (name "unconnected-(CON6-PadD+)") (class "Default")
      (node (ref "CON6") (pin "D+") (pinfunction "D+_D+") (pintype "bidirectional"))
    )
    (net (code "56") (name "unconnected-(CON6-PadD-)") (class "Default")
      (node (ref "CON6") (pin "D-") (pinfunction "D-_D-") (pintype "bidirectional"))
    )
    (net (code "57") (name "unconnected-(CON7-Pad1)") (class "Default")
      (node (ref "CON7") (pin "1") (pinfunction "1_1") (pintype "passive"))
    )
    (net (code "58") (name "unconnected-(IC1-NC-Pad3)") (class "Default")
      (node (ref "IC1") (pin "3") (pinfunction "NC_3") (pintype "bidirectional"))
    )
    (net (code "59") (name "unconnected-(IC2-CHRG-Pad1)") (class "Default")
      (node (ref "IC2") (pin "1") (pinfunction "CHRG_1") (pintype "bidirectional"))
    )
    (net (code "60") (name "unconnected-(IC3-BY-Pad4)") (class "Default")
      (node (ref "IC3") (pin "4") (pinfunction "BY_4") (pintype "bidirectional"))
    )
    (net (code "61") (name "unconnected-(MODULE2-PIO2-Pad25)") (class "Default")
      (node (ref "MODULE2") (pin "25") (pinfunction "PIO2_25") (pintype "bidirectional"))
    )
    (net (code "62") (name "unconnected-(MODULE2-PIO3-Pad26)") (class "Default")
      (node (ref "MODULE2") (pin "26") (pinfunction "PIO3_26") (pintype "bidirectional"))
    )
    (net (code "63") (name "unconnected-(MODULE2-PIO4-Pad27)") (class "Default")
      (node (ref "MODULE2") (pin "27") (pinfunction "PIO4_27") (pintype "bidirectional"))
    )
    (net (code "64") (name "unconnected-(MODULE2-PIO5-Pad28)") (class "Default")
      (node (ref "MODULE2") (pin "28") (pinfunction "PIO5_28") (pintype "bidirectional"))
    )
    (net (code "65") (name "unconnected-(MODULE2-PIO6-Pad29)") (class "Default")
      (node (ref "MODULE2") (pin "29") (pinfunction "PIO6_29") (pintype "bidirectional"))
    )
    (net (code "66") (name "unconnected-(MODULE2-PIO7-Pad30)") (class "Default")
      (node (ref "MODULE2") (pin "30") (pinfunction "PIO7_30") (pintype "bidirectional"))
    )
    (net (code "67") (name "unconnected-(MODULE2-PIO8-Pad31)") (class "Default")
      (node (ref "MODULE2") (pin "31") (pinfunction "PIO8_31") (pintype "bidirectional"))
    )
    (net (code "68") (name "unconnected-(MODULE2-PIO9-Pad32)") (class "Default")
      (node (ref "MODULE2") (pin "32") (pinfunction "PIO9_32") (pintype "bidirectional"))
    )
    (net (code "69") (name "unconnected-(MODULE2-PIO10\\-Pad33)") (class "Default")
      (node (ref "MODULE2") (pin "33") (pinfunction "PIO10\\_33") (pintype "bidirectional"))
    )
    (net (code "70") (name "unconnected-(MODULE2-PIO11-Pad34)") (class "Default")
      (node (ref "MODULE2") (pin "34") (pinfunction "PIO11_34") (pintype "bidirectional"))
    )
    (net (code "71") (name "unconnected-(MODULE2-Pad5)") (class "Default")
      (node (ref "MODULE2") (pin "5") (pinfunction "5_5") (pintype "bidirectional"))
    )
    (net (code "72") (name "unconnected-(MODULE2-Pad6)") (class "Default")
      (node (ref "MODULE2") (pin "6") (pinfunction "6_6") (pintype "bidirectional"))
    )
    (net (code "73") (name "unconnected-(MODULE2-Pad7)") (class "Default")
      (node (ref "MODULE2") (pin "7") (pinfunction "7_7") (pintype "bidirectional"))
    )
    (net (code "74") (name "unconnected-(MODULE2-Pad8)") (class "Default")
      (node (ref "MODULE2") (pin "8") (pinfunction "8_8") (pintype "bidirectional"))
    )
    (net (code "75") (name "unconnected-(MODULE2-Pad9)") (class "Default")
      (node (ref "MODULE2") (pin "9") (pinfunction "9_9") (pintype "bidirectional"))
    )
    (net (code "76") (name "unconnected-(MODULE2-Pad10)") (class "Default")
      (node (ref "MODULE2") (pin "10") (pinfunction "10_10") (pintype "bidirectional"))
    )
    (net (code "77") (name "unconnected-(MODULE2-Pad16)") (class "Default")
      (node (ref "MODULE2") (pin "16") (pinfunction "16_16") (pintype "bidirectional"))
    )
    (net (code "78") (name "unconnected-(MODULE2-Pad17)") (class "Default")
      (node (ref "MODULE2") (pin "17") (pinfunction "17_17") (pintype "bidirectional"))
    )
    (net (code "79") (name "unconnected-(MODULE2-Pad18)") (class "Default")
      (node (ref "MODULE2") (pin "18") (pinfunction "18_18") (pintype "bidirectional"))
    )
    (net (code "80") (name "unconnected-(MODULE2-Pad19)") (class "Default")
      (node (ref "MODULE2") (pin "19") (pinfunction "19_19") (pintype "bidirectional"))
    )
    (net (code "81") (name "unconnected-(MODULE2-RESETB-Pad11)") (class "Default")
      (node (ref "MODULE2") (pin "11") (pinfunction "RESETB_11") (pintype "bidirectional"))
    )
    (net (code "82") (name "unconnected-(MODULE2-UART_CTS-Pad3)") (class "Default")
      (node (ref "MODULE2") (pin "3") (pinfunction "UART_CTS_3") (pintype "bidirectional"))
    )
    (net (code "83") (name "unconnected-(MODULE2-UART_RTS-Pad4)") (class "Default")
      (node (ref "MODULE2") (pin "4") (pinfunction "UART_RTS_4") (pintype "bidirectional"))
    )
  )
)
